# fuse-a-2.net
KiCad netlist of a schematic drawn in EAGLE
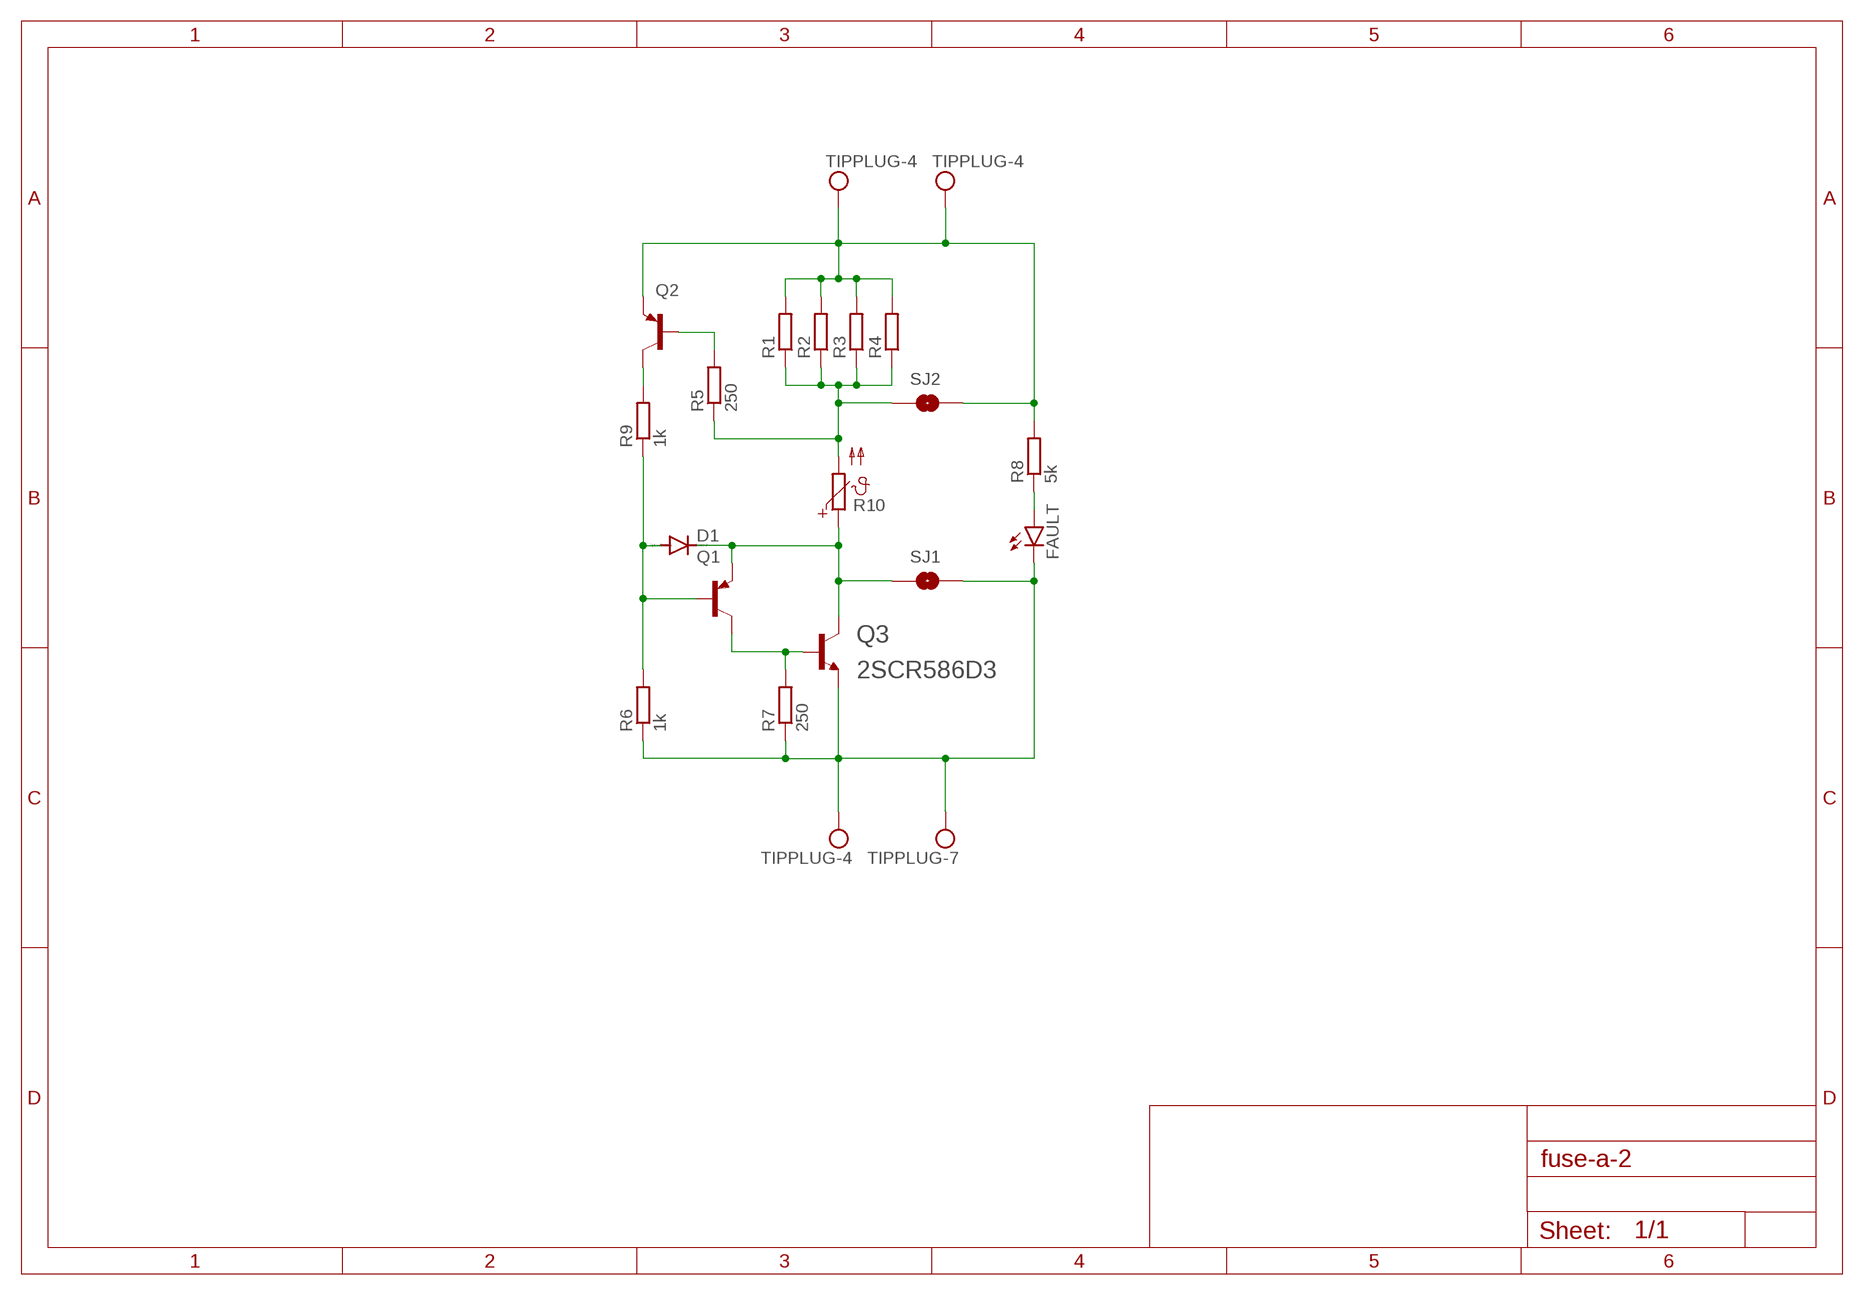
[diagram p0: schematic, sheet 1]

(export (version "E")
  (design (tool "Eeschema 10.0.6"))
  (components
    (comp (ref "D1")
      (value "DIODE-MINIMELF")
      (footprint "eagle-import:MINIMELF")
      (libsource (lib "eagle-import") (part "DIODE-MINIMELF"))
    )
    (comp (ref "FAULT")
      (value "LEDCHIPLED_0603")
      (footprint "eagle-import:CHIPLED_0603")
      (libsource (lib "eagle-import") (part "LEDCHIPLED_0603"))
    )
    (comp (ref "Q1")
      (value "BCX71SMD")
      (footprint "eagle-import:SOT23")
      (libsource (lib "eagle-import") (part "BCX71SMD"))
    )
    (comp (ref "Q2")
      (value "BCX71SMD")
      (footprint "eagle-import:SOT23")
      (libsource (lib "eagle-import") (part "BCX71SMD"))
    )
    (comp (ref "Q3")
      (value "2SCR586D3")
      (footprint "eagle-import:D-PAK_TO252AA")
      (libsource (lib "eagle-import") (part "2SCR586D3TL1"))
    )
    (comp (ref "R1")
      (value "R-EU_R2512")
      (footprint "eagle-import:R2512")
      (libsource (lib "eagle-import") (part "R-EU_R2512"))
    )
    (comp (ref "R2")
      (value "R-EU_R2512")
      (footprint "eagle-import:R2512")
      (libsource (lib "eagle-import") (part "R-EU_R2512"))
    )
    (comp (ref "R3")
      (value "R-EU_R2512")
      (footprint "eagle-import:R2512")
      (libsource (lib "eagle-import") (part "R-EU_R2512"))
    )
    (comp (ref "R4")
      (value "R-EU_R2512")
      (footprint "eagle-import:R2512")
      (libsource (lib "eagle-import") (part "R-EU_R2512"))
    )
    (comp (ref "R5")
      (value "250")
      (footprint "eagle-import:R0805")
      (libsource (lib "eagle-import") (part "R-EU_R0805"))
    )
    (comp (ref "R6")
      (value "1k")
      (footprint "eagle-import:R0805")
      (libsource (lib "eagle-import") (part "R-EU_R0805"))
    )
    (comp (ref "R7")
      (value "250")
      (footprint "eagle-import:R0805")
      (libsource (lib "eagle-import") (part "R-EU_R0805"))
    )
    (comp (ref "R8")
      (value "5k")
      (footprint "eagle-import:R0805")
      (libsource (lib "eagle-import") (part "R-EU_R0805"))
    )
    (comp (ref "R9")
      (value "1k")
      (footprint "eagle-import:R0805")
      (libsource (lib "eagle-import") (part "R-EU_R0805"))
    )
    (comp (ref "R10")
      (value "PTC_1812")
      (footprint "eagle-import:PTC1812")
      (libsource (lib "eagle-import") (part "PTC_1812"))
    )
    (comp (ref "SJ1")
      (value "SJRND2")
      (footprint "eagle-import:SJ_RND2")
      (libsource (lib "eagle-import") (part "SJRND2"))
    )
    (comp (ref "SJ2")
      (value "SJRND2")
      (footprint "eagle-import:SJ_RND2")
      (libsource (lib "eagle-import") (part "SJRND2"))
    )
    (comp (ref "U$1")
      (value "TIPPLUG-4")
      (footprint "eagle-import:BANANAPLUG-4-LUG")
      (libsource (lib "eagle-import") (part "TIPPLUG-4"))
    )
    (comp (ref "U$2")
      (value "TIPPLUG-4")
      (footprint "eagle-import:BANANAPLUG-4-LUG")
      (libsource (lib "eagle-import") (part "TIPPLUG-4"))
    )
    (comp (ref "U$3")
      (value "TIPPLUG-7")
      (footprint "eagle-import:BANANAPLUG-7-LUG")
      (libsource (lib "eagle-import") (part "TIPPLUG-7"))
    )
    (comp (ref "U$4")
      (value "TIPPLUG-4")
      (footprint "eagle-import:BANANAPLUG-4-LUG")
      (libsource (lib "eagle-import") (part "TIPPLUG-4"))
    )
  )
  (nets
    (net (code "1") (name "Net-(FAULT-PadA)") (class "Default")
      (node (ref "FAULT") (pin "A") (pinfunction "A_A") (pintype "passive"))
      (node (ref "R8") (pin "1") (pinfunction "1_1") (pintype "passive"))
    )
    (net (code "2") (name "Net-(Q1-B)") (class "Default")
      (node (ref "D1") (pin "A") (pinfunction "A_A") (pintype "passive"))
      (node (ref "Q1") (pin "1") (pinfunction "B_1") (pintype "passive"))
      (node (ref "R6") (pin "2") (pinfunction "2_2") (pintype "passive"))
      (node (ref "R9") (pin "1") (pinfunction "1_1") (pintype "passive"))
    )
    (net (code "3") (name "Net-(Q1-C)") (class "Default")
      (node (ref "Q1") (pin "3") (pinfunction "C_3") (pintype "passive"))
      (node (ref "Q3") (pin "1") (pinfunction "B_1") (pintype "passive"))
      (node (ref "R7") (pin "2") (pinfunction "2_2") (pintype "passive"))
    )
    (net (code "4") (name "Net-(Q1-E)") (class "Default")
      (node (ref "D1") (pin "C") (pinfunction "C_C") (pintype "passive"))
      (node (ref "Q1") (pin "2") (pinfunction "E_2") (pintype "passive"))
      (node (ref "Q3") (pin "4") (pinfunction "C_4") (pintype "passive"))
      (node (ref "R10") (pin "1") (pinfunction "1_1") (pintype "passive"))
      (node (ref "SJ1") (pin "P$1") (pinfunction "1_P$1") (pintype "passive"))
    )
    (net (code "5") (name "Net-(Q2-B)") (class "Default")
      (node (ref "Q2") (pin "1") (pinfunction "B_1") (pintype "passive"))
      (node (ref "R5") (pin "2") (pinfunction "2_2") (pintype "passive"))
    )
    (net (code "6") (name "Net-(Q2-C)") (class "Default")
      (node (ref "Q2") (pin "3") (pinfunction "C_3") (pintype "passive"))
      (node (ref "R9") (pin "2") (pinfunction "2_2") (pintype "passive"))
    )
    (net (code "7") (name "Net-(Q2-E)") (class "Default")
      (node (ref "Q2") (pin "2") (pinfunction "E_2") (pintype "passive"))
      (node (ref "R1") (pin "2") (pinfunction "2_2") (pintype "passive"))
      (node (ref "R2") (pin "2") (pinfunction "2_2") (pintype "passive"))
      (node (ref "R3") (pin "2") (pinfunction "2_2") (pintype "passive"))
      (node (ref "R4") (pin "2") (pinfunction "2_2") (pintype "passive"))
      (node (ref "R8") (pin "2") (pinfunction "2_2") (pintype "passive"))
      (node (ref "SJ2") (pin "P$2") (pinfunction "2_P$2") (pintype "passive"))
      (node (ref "U$1") (pin "4MM") (pinfunction "$1_4MM") (pintype "passive"))
      (node (ref "U$4") (pin "4MM") (pinfunction "$1_4MM") (pintype "passive"))
    )
    (net (code "8") (name "Net-(Q3-E)") (class "Default")
      (node (ref "FAULT") (pin "C") (pinfunction "C_C") (pintype "passive"))
      (node (ref "Q3") (pin "3") (pinfunction "E_3") (pintype "passive"))
      (node (ref "R6") (pin "1") (pinfunction "1_1") (pintype "passive"))
      (node (ref "R7") (pin "1") (pinfunction "1_1") (pintype "passive"))
      (node (ref "SJ1") (pin "P$2") (pinfunction "2_P$2") (pintype "passive"))
      (node (ref "U$2") (pin "4MM") (pinfunction "$1_4MM") (pintype "passive"))
      (node (ref "U$3") (pin "7MM") (pinfunction "$1_7MM") (pintype "passive"))
    )
    (net (code "9") (name "Net-(SJ2-1)") (class "Default")
      (node (ref "R1") (pin "1") (pinfunction "1_1") (pintype "passive"))
      (node (ref "R10") (pin "2") (pinfunction "2_2") (pintype "passive"))
      (node (ref "R2") (pin "1") (pinfunction "1_1") (pintype "passive"))
      (node (ref "R3") (pin "1") (pinfunction "1_1") (pintype "passive"))
      (node (ref "R4") (pin "1") (pinfunction "1_1") (pintype "passive"))
      (node (ref "R5") (pin "1") (pinfunction "1_1") (pintype "passive"))
      (node (ref "SJ2") (pin "P$1") (pinfunction "1_P$1") (pintype "passive"))
    )
  )
)
